# Motor.net
KiCad netlist of a schematic drawn in Altium Designer
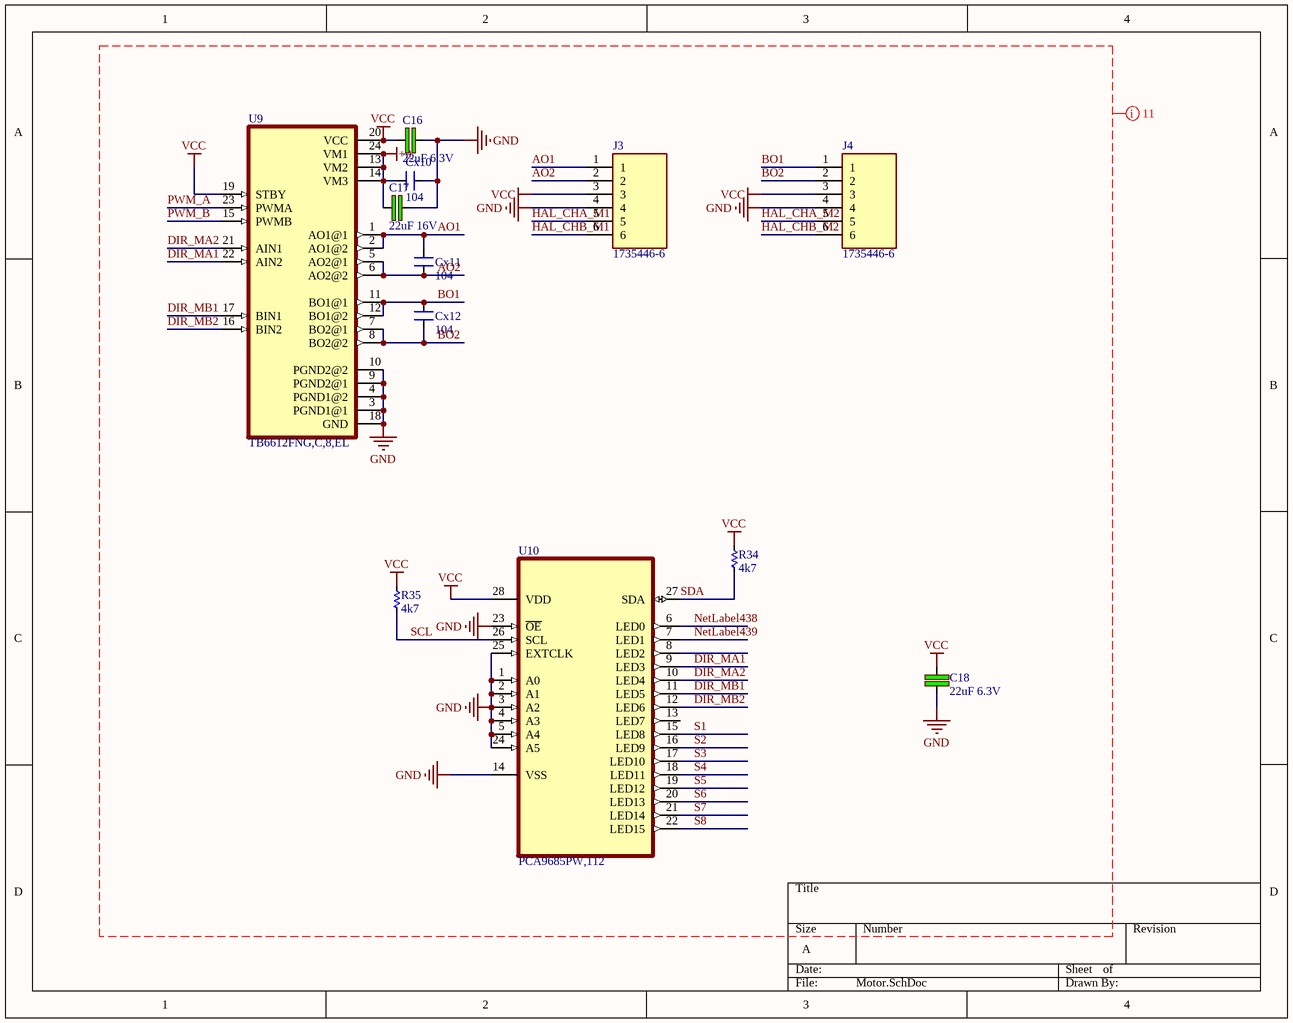
[diagram p0: Motor.SchDoc]

(export (version "E")
  (design (tool "Eeschema 10.0.6"))
  (components
    (comp (ref "C16")
      (value "22uF 6.3V")
      (footprint "CN-SMD-1206")
      (description "Cap SMD 1206 >5V")
      (libsource (lib "Library AL") (part "C"))
    )
    (comp (ref "C17")
      (value "22uF 16V")
      (footprint "CN-SMD-1206")
      (description "Cap SMD 1206 >5V")
      (libsource (lib "") (part "C_2"))
    )
    (comp (ref "C18")
      (value "22uF 6.3V")
      (footprint "CN-SMD-1206")
      (description "Cap SMD 1206 >5V")
      (libsource (lib "") (part "C_1"))
    )
    (comp (ref "Cx10") (value "104") (footprint "CN-SMD-0603") (libsource (lib "LIBRARY") (part "CN")))
    (comp (ref "Cx11") (value "104") (footprint "CN-SMD-0603") (libsource (lib "LIBRARY") (part "CN")))
    (comp (ref "Cx12") (value "104") (footprint "CN-SMD-0603") (libsource (lib "LIBRARY") (part "CN")))
    (comp (ref "J3")
      (value "1735446-6")
      (footprint "TE_1735446-6")
      (description "2MM PITCH HPI POST HEADER, VERTICAL, 6P")
      (fields (field (name "MF") "TE Connectivity"))
      (libsource (lib "CON_6P1") (part "1735446-6"))
    )
    (comp (ref "J4")
      (value "1735446-6")
      (footprint "TE_1735446-6")
      (description "2MM PITCH HPI POST HEADER, VERTICAL, 6P")
      (fields (field (name "MF") "TE Connectivity"))
      (libsource (lib "CON_6P1") (part "1735446-6"))
    )
    (comp (ref "R34")
      (value "4k7")
      (footprint "RES-SMD-0603")
      (description "Resistor")
      (fields
        (field (name "MANUFACTURER") "Generic Components")
        (field (name "PUBLISHER") "Altium Hobart Technology Centre")
      )
      (libsource (lib "My Library") (part "Res-SMD"))
    )
    (comp (ref "R35")
      (value "4k7")
      (footprint "RES-SMD-0603")
      (description "Resistor")
      (fields
        (field (name "MANUFACTURER") "Generic Components")
        (field (name "PUBLISHER") "Altium Hobart Technology Centre")
      )
      (libsource (lib "My Library") (part "Res-SMD"))
    )
    (comp (ref "U9")
      (value "TB6612FNG,C,8,EL")
      (footprint "SOP65P760X160-24N")
      (description "Motor Driver Power MOSFET Parallel 24-SSOP")
      (fields (field (name "DIGI-KEY_PART_NUMBER") "TB6612FNGC8ELCT-ND") (field (name "MF") "Toshiba"))
      (libsource (lib "TB6612FNG_C_8_EL") (part "TB6612FNG,C,8,EL"))
    )
    (comp (ref "U10")
      (value "PCA9685PW,112")
      (footprint "SOP65P640X110-28N")
      (description "LED Driver IC 16 Output Linear PWM Dimming 25mA 28-TSSOP")
      (fields (field (name "MF") "NXP USA") (field (name "DIGI-KEY_PART_NUMBER") "568-8366-5-ND"))
      (libsource (lib "PCA9685PW_112") (part "PCA9685PW,112"))
    )
  )
  (nets
    (net (code "1") (name "+9") (class "Default")
      (node (ref "C17") (pin "1") (pinfunction "1_1") (pintype "passive"))
      (node (ref "Cx10") (pin "2") (pinfunction "2_2") (pintype "passive"))
      (node (ref "U9") (pin "13") (pinfunction "VM2_13") (pintype "power_in"))
      (node (ref "U9") (pin "14") (pinfunction "VM3_14") (pintype "power_in"))
      (node (ref "U9") (pin "24") (pinfunction "VM1_24") (pintype "power_in"))
    )
    (net (code "2") (name "/AO1") (class "Default")
      (node (ref "Cx11") (pin "1") (pinfunction "1_1") (pintype "passive"))
      (node (ref "J3") (pin "1") (pinfunction "1_1") (pintype "passive"))
      (node (ref "U9") (pin "1") (pinfunction "AO1@1_1") (pintype "output"))
      (node (ref "U9") (pin "2") (pinfunction "AO1@2_2") (pintype "output"))
    )
    (net (code "3") (name "/AO2") (class "Default")
      (node (ref "Cx11") (pin "2") (pinfunction "2_2") (pintype "passive"))
      (node (ref "J3") (pin "2") (pinfunction "2_2") (pintype "passive"))
      (node (ref "U9") (pin "5") (pinfunction "AO2@1_5") (pintype "output"))
      (node (ref "U9") (pin "6") (pinfunction "AO2@2_6") (pintype "output"))
    )
    (net (code "4") (name "/BO1") (class "Default")
      (node (ref "Cx12") (pin "1") (pinfunction "1_1") (pintype "passive"))
      (node (ref "J4") (pin "1") (pinfunction "1_1") (pintype "passive"))
      (node (ref "U9") (pin "11") (pinfunction "BO1@1_11") (pintype "output"))
      (node (ref "U9") (pin "12") (pinfunction "BO1@2_12") (pintype "output"))
    )
    (net (code "5") (name "/BO2") (class "Default")
      (node (ref "Cx12") (pin "2") (pinfunction "2_2") (pintype "passive"))
      (node (ref "J4") (pin "2") (pinfunction "2_2") (pintype "passive"))
      (node (ref "U9") (pin "7") (pinfunction "BO2@1_7") (pintype "output"))
      (node (ref "U9") (pin "8") (pinfunction "BO2@2_8") (pintype "output"))
    )
    (net (code "6") (name "/DIR_MA1") (class "Default")
      (node (ref "U10") (pin "9") (pinfunction "LED3_9") (pintype "output"))
      (node (ref "U9") (pin "22") (pinfunction "AIN2_22") (pintype "input"))
    )
    (net (code "7") (name "/DIR_MA2") (class "Default")
      (node (ref "U10") (pin "10") (pinfunction "LED4_10") (pintype "output"))
      (node (ref "U9") (pin "21") (pinfunction "AIN1_21") (pintype "input"))
    )
    (net (code "8") (name "/DIR_MB1") (class "Default")
      (node (ref "U10") (pin "11") (pinfunction "LED5_11") (pintype "output"))
      (node (ref "U9") (pin "17") (pinfunction "BIN1_17") (pintype "input"))
    )
    (net (code "9") (name "/DIR_MB2") (class "Default")
      (node (ref "U10") (pin "12") (pinfunction "LED6_12") (pintype "output"))
      (node (ref "U9") (pin "16") (pinfunction "BIN2_16") (pintype "input"))
    )
    (net (code "10") (name "/HAL_CHA_M1") (class "Default")
      (node (ref "J3") (pin "5") (pinfunction "5_5") (pintype "passive"))
    )
    (net (code "11") (name "/HAL_CHA_M2") (class "Default")
      (node (ref "J4") (pin "5") (pinfunction "5_5") (pintype "passive"))
    )
    (net (code "12") (name "/HAL_CHB_M1") (class "Default")
      (node (ref "J3") (pin "6") (pinfunction "6_6") (pintype "passive"))
    )
    (net (code "13") (name "/HAL_CHB_M2") (class "Default")
      (node (ref "J4") (pin "6") (pinfunction "6_6") (pintype "passive"))
    )
    (net (code "14") (name "/NetLabel438") (class "Default")
      (node (ref "U10") (pin "6") (pinfunction "LED0_6") (pintype "output"))
    )
    (net (code "15") (name "/NetLabel439") (class "Default")
      (node (ref "U10") (pin "7") (pinfunction "LED1_7") (pintype "output"))
    )
    (net (code "16") (name "/PWM_A") (class "Default")
      (node (ref "U9") (pin "23") (pinfunction "PWMA_23") (pintype "input"))
    )
    (net (code "17") (name "/PWM_B") (class "Default")
      (node (ref "U9") (pin "15") (pinfunction "PWMB_15") (pintype "input"))
    )
    (net (code "18") (name "/S1") (class "Default")
      (node (ref "U10") (pin "15") (pinfunction "LED8_15") (pintype "output"))
    )
    (net (code "19") (name "/S2") (class "Default")
      (node (ref "U10") (pin "16") (pinfunction "LED9_16") (pintype "output"))
    )
    (net (code "20") (name "/S3") (class "Default")
      (node (ref "U10") (pin "17") (pinfunction "LED10_17") (pintype "output"))
    )
    (net (code "21") (name "/S4") (class "Default")
      (node (ref "U10") (pin "18") (pinfunction "LED11_18") (pintype "output"))
    )
    (net (code "22") (name "/S5") (class "Default")
      (node (ref "U10") (pin "19") (pinfunction "LED12_19") (pintype "output"))
    )
    (net (code "23") (name "/S6") (class "Default")
      (node (ref "U10") (pin "20") (pinfunction "LED13_20") (pintype "output"))
    )
    (net (code "24") (name "/S7") (class "Default")
      (node (ref "U10") (pin "21") (pinfunction "LED14_21") (pintype "output"))
    )
    (net (code "25") (name "/S8") (class "Default")
      (node (ref "U10") (pin "22") (pinfunction "LED15_22") (pintype "output"))
    )
    (net (code "26") (name "/SCL") (class "Default")
      (node (ref "R35") (pin "1") (pinfunction "1_1") (pintype "passive"))
      (node (ref "U10") (pin "26") (pinfunction "SCL_26") (pintype "input"))
    )
    (net (code "27") (name "/SDA") (class "Default")
      (node (ref "R34") (pin "1") (pinfunction "1_1") (pintype "passive"))
      (node (ref "U10") (pin "27") (pinfunction "SDA_27") (pintype "bidirectional"))
    )
    (net (code "28") (name "GND") (class "Default")
      (node (ref "C16") (pin "1") (pinfunction "1_1") (pintype "passive"))
      (node (ref "C17") (pin "2") (pinfunction "2_2") (pintype "passive"))
      (node (ref "C18") (pin "1") (pinfunction "1_1") (pintype "passive"))
      (node (ref "Cx10") (pin "1") (pinfunction "1_1") (pintype "passive"))
      (node (ref "J3") (pin "4") (pinfunction "4_4") (pintype "passive"))
      (node (ref "J4") (pin "4") (pinfunction "4_4") (pintype "passive"))
      (node (ref "U10") (pin "1") (pinfunction "A0_1") (pintype "input"))
      (node (ref "U10") (pin "14") (pinfunction "VSS_14") (pintype "passive"))
      (node (ref "U10") (pin "2") (pinfunction "A1_2") (pintype "input"))
      (node (ref "U10") (pin "23") (pinfunction "~{OE}_23") (pintype "input"))
      (node (ref "U10") (pin "24") (pinfunction "A5_24") (pintype "input"))
      (node (ref "U10") (pin "25") (pinfunction "EXTCLK_25") (pintype "input"))
      (node (ref "U10") (pin "3") (pinfunction "A2_3") (pintype "input"))
      (node (ref "U10") (pin "4") (pinfunction "A3_4") (pintype "input"))
      (node (ref "U10") (pin "5") (pinfunction "A4_5") (pintype "input"))
      (node (ref "U9") (pin "10") (pinfunction "PGND2@2_10") (pintype "passive"))
      (node (ref "U9") (pin "18") (pinfunction "GND_18") (pintype "passive"))
      (node (ref "U9") (pin "3") (pinfunction "PGND1@1_3") (pintype "passive"))
      (node (ref "U9") (pin "4") (pinfunction "PGND1@2_4") (pintype "passive"))
      (node (ref "U9") (pin "9") (pinfunction "PGND2@1_9") (pintype "passive"))
    )
    (net (code "29") (name "VCC") (class "Default")
      (node (ref "C16") (pin "2") (pinfunction "2_2") (pintype "passive"))
      (node (ref "C18") (pin "2") (pinfunction "2_2") (pintype "passive"))
      (node (ref "J3") (pin "3") (pinfunction "3_3") (pintype "passive"))
      (node (ref "J4") (pin "3") (pinfunction "3_3") (pintype "passive"))
      (node (ref "R34") (pin "2") (pinfunction "2_2") (pintype "passive"))
      (node (ref "R35") (pin "2") (pinfunction "2_2") (pintype "passive"))
      (node (ref "U10") (pin "28") (pinfunction "VDD_28") (pintype "power_in"))
      (node (ref "U9") (pin "19") (pinfunction "STBY_19") (pintype "input"))
      (node (ref "U9") (pin "20") (pinfunction "VCC_20") (pintype "power_in"))
    )
    (net (code "30") (name "unconnected-(U10-LED2-Pad8)") (class "Default")
      (node (ref "U10") (pin "8") (pinfunction "LED2_8") (pintype "output"))
    )
    (net (code "31") (name "unconnected-(U10-LED7-Pad13)") (class "Default")
      (node (ref "U10") (pin "13") (pinfunction "LED7_13") (pintype "output"))
    )
  )
)
